# Sheet1.net
KiCad netlist of a schematic drawn in Altium Designer
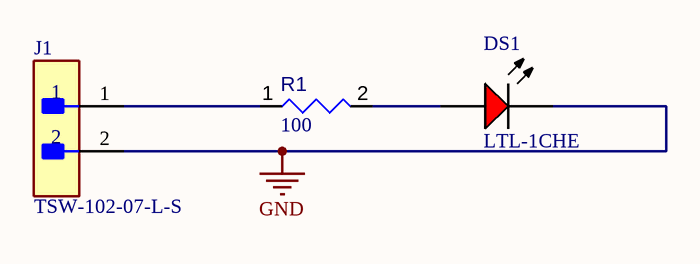
[diagram p0: Sheet1.SchDoc]

(export (version "E")
  (design (tool "Eeschema 10.0.6"))
  (components
    (comp (ref "DS1")
      (value "LTL-1CHE")
      (footprint "INDPR60-254-520X380X650")
      (description "LED Uni-Color Red, 100 mW, 30 mA, -55 to 100 degC, 2-Pin THD, RoHS, Bulk")
      (fields (field (name "MANUFACTURER") "Lite-On"))
      (libsource (lib "Ufscar - Universidade Federal de São Carlos") (part "LED-RED-AK-2"))
    )
    (comp (ref "J1")
      (value "TSW-102-07-L-S")
      (footprint "FP-TSW-102-07-L-S-MFG")
      (description "CONN HEADER VERT 2POS 2.54MM")
      (libsource (lib "Altium Content Vault") (part "3bc925449376181038e59eaffc5286c"))
    )
    (comp (ref "R1")
      (value "100")
      (footprint "RESA60-630X240")
      (description "Axial Resistor, 100 Ohm, +/- 1%, 0.25 W, -55 to 155 degC, 2-Pin THD, RoHS, Bulk")
      (fields (field (name "MANUFACTURER") "Yageo") (field (name "TOLERANCE") "1%"))
      (libsource (lib "Ufscar - Universidade Federal de São Carlos") (part "RES-2"))
    )
  )
  (nets
    (net (code "1") (name "GND") (class "Default")
      (node (ref "DS1") (pin "2") (pinfunction "K_2") (pintype "passive"))
      (node (ref "J1") (pin "2") (pinfunction "2_2") (pintype "passive"))
    )
    (net (code "2") (name "Net-(DS1-A)") (class "Default")
      (node (ref "DS1") (pin "1") (pinfunction "A_1") (pintype "passive"))
      (node (ref "R1") (pin "2") (pinfunction "2_2") (pintype "passive"))
    )
    (net (code "3") (name "Net-(J1-Pad1)") (class "Default")
      (node (ref "J1") (pin "1") (pinfunction "1_1") (pintype "passive"))
      (node (ref "R1") (pin "1") (pinfunction "1_1") (pintype "passive"))
    )
  )
)
